# SP3_PMIC.net
KiCad netlist of a schematic drawn in Altium Designer
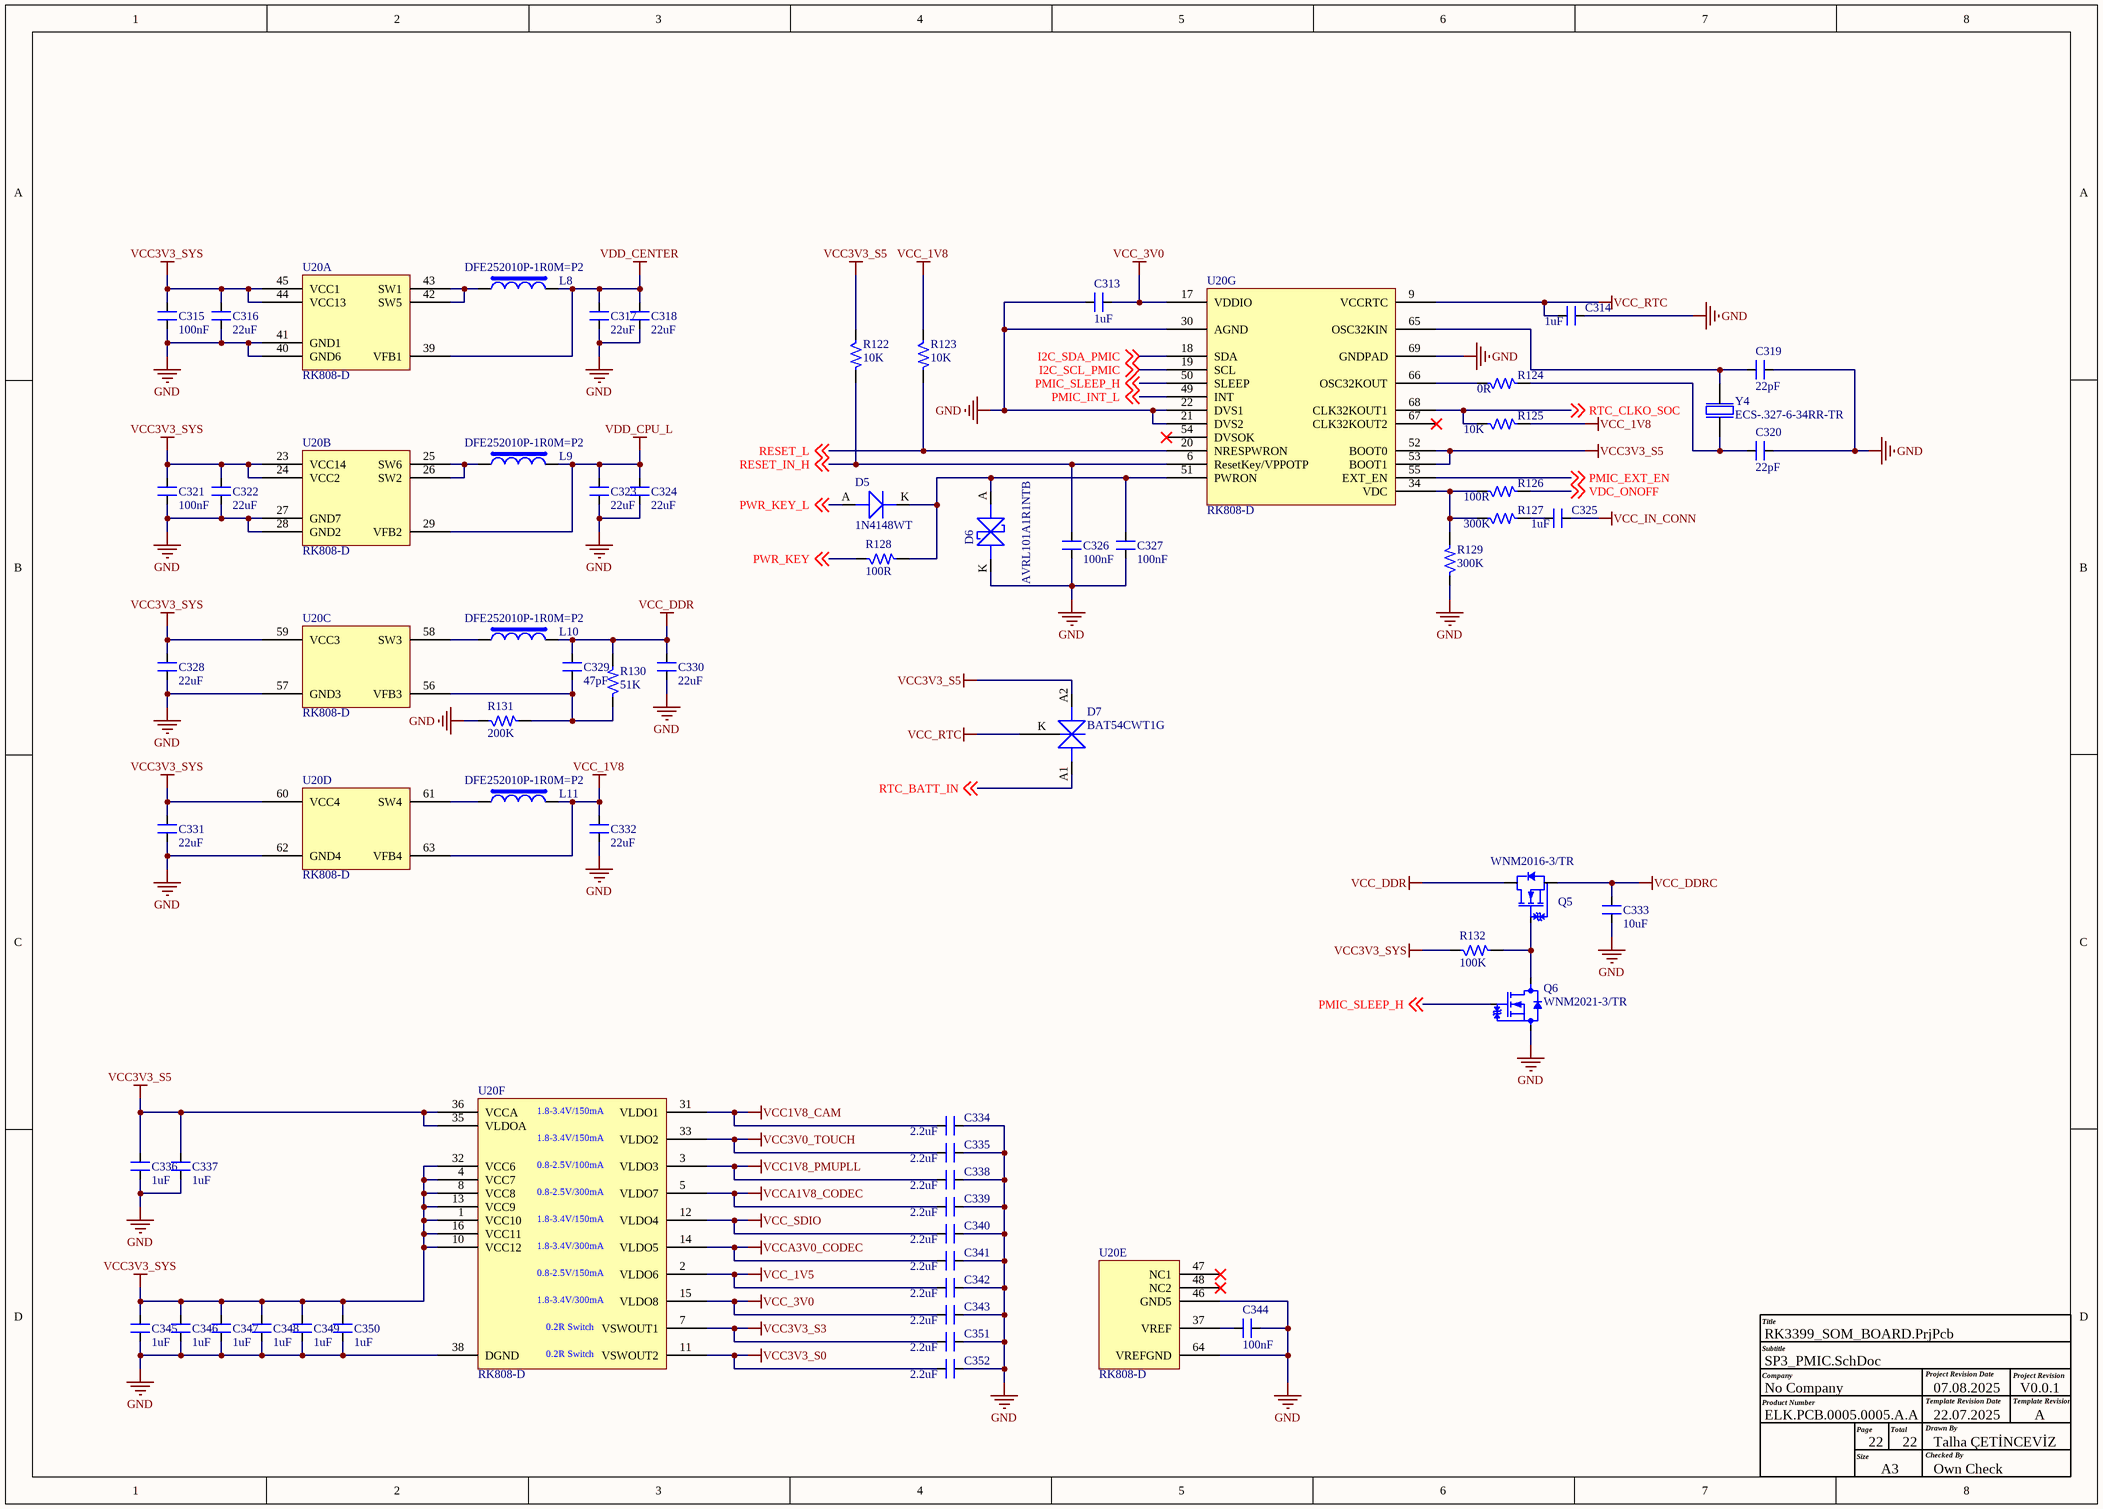
[diagram p0: SP3_PMIC.SchDoc]

(export (version "E")
  (design (tool "Eeschema 10.0.6"))
  (components
    (comp (ref "C313")
      (value "1uF")
      (footprint "CAP_0402")
      (description "1µF ±10% 16V Ceramic Capacitor X5R 0402 (1005 Metric)")
      (fields
        (field (name "MANUFACTURER") "Knowles Novacap")
        (field (name "MANUFACTURER PART NUMBER") "0402BW105K160YT")
      )
      (libsource (lib "EsteemPCB_SOM_Course_intlib") (part "CAP_1uF-16V-10%-0402"))
    )
    (comp (ref "C314")
      (value "1uF")
      (footprint "CAP_0402")
      (description "1µF ±10% 16V Ceramic Capacitor X5R 0402 (1005 Metric)")
      (fields
        (field (name "MANUFACTURER") "Knowles Novacap")
        (field (name "MANUFACTURER PART NUMBER") "0402BW105K160YT")
      )
      (libsource (lib "EsteemPCB_SOM_Course_intlib") (part "CAP_1uF-16V-10%-0402"))
    )
    (comp (ref "C315")
      (value "100nF")
      (footprint "CAP_0402")
      (description "0.1µF ±10% 25V Ceramic Capacitor X7R 0402 (1005 Metric)")
      (fields
        (field (name "MANUFACTURER") "Walsin Technology Corporation")
        (field (name "MANUFACTURER PART NUMBER") "0402B104K250CT")
      )
      (libsource (lib "EsteemPCB_SOM_Course_intlib") (part "CAP_100nF-25V-10%-0402"))
    )
    (comp (ref "C316")
      (value "22uF")
      (footprint "CAP_0603")
      (description "22µF ±20% 10V Ceramic Capacitor X5R 0603 (1608 Metric)")
      (fields
        (field (name "MANUFACTURER") "Murata Electronics")
        (field (name "MANUFACTURER PART NUMBER") "GRM188R61A226ME15D")
      )
      (libsource (lib "EsteemPCB_SOM_Course_intlib") (part "CAP_22uF-10V-20%-0603"))
    )
    (comp (ref "C317")
      (value "22uF")
      (footprint "CAP_0603")
      (description "22µF ±20% 10V Ceramic Capacitor X5R 0603 (1608 Metric)")
      (fields
        (field (name "MANUFACTURER") "Murata Electronics")
        (field (name "MANUFACTURER PART NUMBER") "GRM188R61A226ME15D")
      )
      (libsource (lib "EsteemPCB_SOM_Course_intlib") (part "CAP_22uF-10V-20%-0603"))
    )
    (comp (ref "C318")
      (value "22uF")
      (footprint "CAP_0603")
      (description "22µF ±20% 10V Ceramic Capacitor X5R 0603 (1608 Metric)")
      (fields
        (field (name "MANUFACTURER") "Murata Electronics")
        (field (name "MANUFACTURER PART NUMBER") "GRM188R61A226ME15D")
      )
      (libsource (lib "EsteemPCB_SOM_Course_intlib") (part "CAP_22uF-10V-20%-0603"))
    )
    (comp (ref "C319")
      (value "22pF")
      (footprint "CAP_0402")
      (description "22pF ±10% 10V Ceramic Capacitor C0G, NP0 0402 (1005 Metric)")
      (fields
        (field (name "MANUFACTURER") "KEMET")
        (field (name "MANUFACTURER PART NUMBER") "C0402C220K8GACTU")
      )
      (libsource (lib "EsteemPCB_SOM_Course_intlib") (part "CAP_22pF-10V-10%-0402"))
    )
    (comp (ref "C320")
      (value "22pF")
      (footprint "CAP_0402")
      (description "22pF ±10% 10V Ceramic Capacitor C0G, NP0 0402 (1005 Metric)")
      (fields
        (field (name "MANUFACTURER") "KEMET")
        (field (name "MANUFACTURER PART NUMBER") "C0402C220K8GACTU")
      )
      (libsource (lib "EsteemPCB_SOM_Course_intlib") (part "CAP_22pF-10V-10%-0402"))
    )
    (comp (ref "C321")
      (value "100nF")
      (footprint "CAP_0402")
      (description "0.1µF ±10% 25V Ceramic Capacitor X7R 0402 (1005 Metric)")
      (fields
        (field (name "MANUFACTURER") "Walsin Technology Corporation")
        (field (name "MANUFACTURER PART NUMBER") "0402B104K250CT")
      )
      (libsource (lib "EsteemPCB_SOM_Course_intlib") (part "CAP_100nF-25V-10%-0402"))
    )
    (comp (ref "C322")
      (value "22uF")
      (footprint "CAP_0603")
      (description "22µF ±20% 10V Ceramic Capacitor X5R 0603 (1608 Metric)")
      (fields
        (field (name "MANUFACTURER") "Murata Electronics")
        (field (name "MANUFACTURER PART NUMBER") "GRM188R61A226ME15D")
      )
      (libsource (lib "EsteemPCB_SOM_Course_intlib") (part "CAP_22uF-10V-20%-0603"))
    )
    (comp (ref "C323")
      (value "22uF")
      (footprint "CAP_0603")
      (description "22µF ±20% 10V Ceramic Capacitor X5R 0603 (1608 Metric)")
      (fields
        (field (name "MANUFACTURER") "Murata Electronics")
        (field (name "MANUFACTURER PART NUMBER") "GRM188R61A226ME15D")
      )
      (libsource (lib "EsteemPCB_SOM_Course_intlib") (part "CAP_22uF-10V-20%-0603"))
    )
    (comp (ref "C324")
      (value "22uF")
      (footprint "CAP_0603")
      (description "22µF ±20% 10V Ceramic Capacitor X5R 0603 (1608 Metric)")
      (fields
        (field (name "MANUFACTURER") "Murata Electronics")
        (field (name "MANUFACTURER PART NUMBER") "GRM188R61A226ME15D")
      )
      (libsource (lib "EsteemPCB_SOM_Course_intlib") (part "CAP_22uF-10V-20%-0603"))
    )
    (comp (ref "C325")
      (value "1uF")
      (footprint "CAP_0402")
      (description "1µF ±10% 16V Ceramic Capacitor X5R 0402 (1005 Metric)")
      (fields
        (field (name "MANUFACTURER") "Knowles Novacap")
        (field (name "MANUFACTURER PART NUMBER") "0402BW105K160YT")
      )
      (libsource (lib "EsteemPCB_SOM_Course_intlib") (part "CAP_1uF-16V-10%-0402"))
    )
    (comp (ref "C326")
      (value "100nF")
      (footprint "CAP_0402")
      (description "0.1µF ±10% 25V Ceramic Capacitor X7R 0402 (1005 Metric)")
      (fields
        (field (name "MANUFACTURER") "Walsin Technology Corporation")
        (field (name "MANUFACTURER PART NUMBER") "0402B104K250CT")
      )
      (libsource (lib "EsteemPCB_SOM_Course_intlib") (part "CAP_100nF-25V-10%-0402"))
    )
    (comp (ref "C327")
      (value "100nF")
      (footprint "CAP_0402")
      (description "0.1µF ±10% 25V Ceramic Capacitor X7R 0402 (1005 Metric)")
      (fields
        (field (name "MANUFACTURER") "Walsin Technology Corporation")
        (field (name "MANUFACTURER PART NUMBER") "0402B104K250CT")
      )
      (libsource (lib "EsteemPCB_SOM_Course_intlib") (part "CAP_100nF-25V-10%-0402"))
    )
    (comp (ref "C328")
      (value "22uF")
      (footprint "CAP_0603")
      (description "22µF ±20% 10V Ceramic Capacitor X5R 0603 (1608 Metric)")
      (fields
        (field (name "MANUFACTURER") "Murata Electronics")
        (field (name "MANUFACTURER PART NUMBER") "GRM188R61A226ME15D")
      )
      (libsource (lib "EsteemPCB_SOM_Course_intlib") (part "CAP_22uF-10V-20%-0603"))
    )
    (comp (ref "C329")
      (value "47pF")
      (footprint "CAP_0402")
      (description "47pF ±10% 10V Ceramic Capacitor C0G, NP0 0402 (1005 Metric)")
      (fields
        (field (name "MANUFACTURER") "KEMET")
        (field (name "MANUFACTURER PART NUMBER") "C0402C470K8GAC7867")
      )
      (libsource (lib "EsteemPCB_SOM_Course_intlib") (part "CAP_47pF-10V-10%-0402"))
    )
    (comp (ref "C330")
      (value "22uF")
      (footprint "CAP_0603")
      (description "22µF ±20% 10V Ceramic Capacitor X5R 0603 (1608 Metric)")
      (fields
        (field (name "MANUFACTURER") "Murata Electronics")
        (field (name "MANUFACTURER PART NUMBER") "GRM188R61A226ME15D")
      )
      (libsource (lib "EsteemPCB_SOM_Course_intlib") (part "CAP_22uF-10V-20%-0603"))
    )
    (comp (ref "C331")
      (value "22uF")
      (footprint "CAP_0603")
      (description "22µF ±20% 10V Ceramic Capacitor X5R 0603 (1608 Metric)")
      (fields
        (field (name "MANUFACTURER") "Murata Electronics")
        (field (name "MANUFACTURER PART NUMBER") "GRM188R61A226ME15D")
      )
      (libsource (lib "EsteemPCB_SOM_Course_intlib") (part "CAP_22uF-10V-20%-0603"))
    )
    (comp (ref "C332")
      (value "22uF")
      (footprint "CAP_0603")
      (description "22µF ±20% 10V Ceramic Capacitor X5R 0603 (1608 Metric)")
      (fields
        (field (name "MANUFACTURER") "Murata Electronics")
        (field (name "MANUFACTURER PART NUMBER") "GRM188R61A226ME15D")
      )
      (libsource (lib "EsteemPCB_SOM_Course_intlib") (part "CAP_22uF-10V-20%-0603"))
    )
    (comp (ref "C333")
      (value "10uF")
      (footprint "CAP_0402")
      (description "10µF ±20% 10V Ceramic Capacitor X5R 0402 (1005 Metric)")
      (fields
        (field (name "MANUFACTURER PART NUMBER") "CL05A106MP5NUNC")
        (field (name "MANUFACTURER") "Samsung Electro-Mechanics")
      )
      (libsource (lib "EsteemPCB_SOM_Course_intlib") (part "CAP_10uF-10V-20%-0402"))
    )
    (comp (ref "C334")
      (value "2.2uF")
      (footprint "CAP_0402")
      (description "2.2µF ±10% 10V Ceramic Capacitor X5R 0402 (1005 Metric)")
      (fields
        (field (name "MANUFACTURER") "Murata Electronics")
        (field (name "MANUFACTURER PART NUMBER") "GRM155R61A225KE95D")
      )
      (libsource (lib "EsteemPCB_SOM_Course_intlib") (part "CAP_2.2uF-10V-10%-0402"))
    )
    (comp (ref "C335")
      (value "2.2uF")
      (footprint "CAP_0402")
      (description "2.2µF ±10% 10V Ceramic Capacitor X5R 0402 (1005 Metric)")
      (fields
        (field (name "MANUFACTURER") "Murata Electronics")
        (field (name "MANUFACTURER PART NUMBER") "GRM155R61A225KE95D")
      )
      (libsource (lib "EsteemPCB_SOM_Course_intlib") (part "CAP_2.2uF-10V-10%-0402"))
    )
    (comp (ref "C336")
      (value "1uF")
      (footprint "CAP_0402")
      (description "1µF ±10% 16V Ceramic Capacitor X5R 0402 (1005 Metric)")
      (fields
        (field (name "MANUFACTURER") "Knowles Novacap")
        (field (name "MANUFACTURER PART NUMBER") "0402BW105K160YT")
      )
      (libsource (lib "EsteemPCB_SOM_Course_intlib") (part "CAP_1uF-16V-10%-0402"))
    )
    (comp (ref "C337")
      (value "1uF")
      (footprint "CAP_0402")
      (description "1µF ±10% 16V Ceramic Capacitor X5R 0402 (1005 Metric)")
      (fields
        (field (name "MANUFACTURER") "Knowles Novacap")
        (field (name "MANUFACTURER PART NUMBER") "0402BW105K160YT")
      )
      (libsource (lib "EsteemPCB_SOM_Course_intlib") (part "CAP_1uF-16V-10%-0402"))
    )
    (comp (ref "C338")
      (value "2.2uF")
      (footprint "CAP_0402")
      (description "2.2µF ±10% 10V Ceramic Capacitor X5R 0402 (1005 Metric)")
      (fields
        (field (name "MANUFACTURER") "Murata Electronics")
        (field (name "MANUFACTURER PART NUMBER") "GRM155R61A225KE95D")
      )
      (libsource (lib "EsteemPCB_SOM_Course_intlib") (part "CAP_2.2uF-10V-10%-0402"))
    )
    (comp (ref "C339")
      (value "2.2uF")
      (footprint "CAP_0402")
      (description "2.2µF ±10% 10V Ceramic Capacitor X5R 0402 (1005 Metric)")
      (fields
        (field (name "MANUFACTURER") "Murata Electronics")
        (field (name "MANUFACTURER PART NUMBER") "GRM155R61A225KE95D")
      )
      (libsource (lib "EsteemPCB_SOM_Course_intlib") (part "CAP_2.2uF-10V-10%-0402"))
    )
    (comp (ref "C340")
      (value "2.2uF")
      (footprint "CAP_0402")
      (description "2.2µF ±10% 10V Ceramic Capacitor X5R 0402 (1005 Metric)")
      (fields
        (field (name "MANUFACTURER") "Murata Electronics")
        (field (name "MANUFACTURER PART NUMBER") "GRM155R61A225KE95D")
      )
      (libsource (lib "EsteemPCB_SOM_Course_intlib") (part "CAP_2.2uF-10V-10%-0402"))
    )
    (comp (ref "C341")
      (value "2.2uF")
      (footprint "CAP_0402")
      (description "2.2µF ±10% 10V Ceramic Capacitor X5R 0402 (1005 Metric)")
      (fields
        (field (name "MANUFACTURER") "Murata Electronics")
        (field (name "MANUFACTURER PART NUMBER") "GRM155R61A225KE95D")
      )
      (libsource (lib "EsteemPCB_SOM_Course_intlib") (part "CAP_2.2uF-10V-10%-0402"))
    )
    (comp (ref "C342")
      (value "2.2uF")
      (footprint "CAP_0402")
      (description "2.2µF ±10% 10V Ceramic Capacitor X5R 0402 (1005 Metric)")
      (fields
        (field (name "MANUFACTURER") "Murata Electronics")
        (field (name "MANUFACTURER PART NUMBER") "GRM155R61A225KE95D")
      )
      (libsource (lib "EsteemPCB_SOM_Course_intlib") (part "CAP_2.2uF-10V-10%-0402"))
    )
    (comp (ref "C343")
      (value "2.2uF")
      (footprint "CAP_0402")
      (description "2.2µF ±10% 10V Ceramic Capacitor X5R 0402 (1005 Metric)")
      (fields
        (field (name "MANUFACTURER") "Murata Electronics")
        (field (name "MANUFACTURER PART NUMBER") "GRM155R61A225KE95D")
      )
      (libsource (lib "EsteemPCB_SOM_Course_intlib") (part "CAP_2.2uF-10V-10%-0402"))
    )
    (comp (ref "C344")
      (value "100nF")
      (footprint "CAP_0402")
      (description "0.1µF ±10% 25V Ceramic Capacitor X7R 0402 (1005 Metric)")
      (fields
        (field (name "MANUFACTURER") "Walsin Technology Corporation")
        (field (name "MANUFACTURER PART NUMBER") "0402B104K250CT")
      )
      (libsource (lib "EsteemPCB_SOM_Course_intlib") (part "CAP_100nF-25V-10%-0402"))
    )
    (comp (ref "C345")
      (value "1uF")
      (footprint "CAP_0402")
      (description "1µF ±10% 16V Ceramic Capacitor X5R 0402 (1005 Metric)")
      (fields
        (field (name "MANUFACTURER") "Knowles Novacap")
        (field (name "MANUFACTURER PART NUMBER") "0402BW105K160YT")
      )
      (libsource (lib "EsteemPCB_SOM_Course_intlib") (part "CAP_1uF-16V-10%-0402"))
    )
    (comp (ref "C346")
      (value "1uF")
      (footprint "CAP_0402")
      (description "1µF ±10% 16V Ceramic Capacitor X5R 0402 (1005 Metric)")
      (fields
        (field (name "MANUFACTURER") "Knowles Novacap")
        (field (name "MANUFACTURER PART NUMBER") "0402BW105K160YT")
      )
      (libsource (lib "EsteemPCB_SOM_Course_intlib") (part "CAP_1uF-16V-10%-0402"))
    )
    (comp (ref "C347")
      (value "1uF")
      (footprint "CAP_0402")
      (description "1µF ±10% 16V Ceramic Capacitor X5R 0402 (1005 Metric)")
      (fields
        (field (name "MANUFACTURER") "Knowles Novacap")
        (field (name "MANUFACTURER PART NUMBER") "0402BW105K160YT")
      )
      (libsource (lib "EsteemPCB_SOM_Course_intlib") (part "CAP_1uF-16V-10%-0402"))
    )
    (comp (ref "C348")
      (value "1uF")
      (footprint "CAP_0402")
      (description "1µF ±10% 16V Ceramic Capacitor X5R 0402 (1005 Metric)")
      (fields
        (field (name "MANUFACTURER") "Knowles Novacap")
        (field (name "MANUFACTURER PART NUMBER") "0402BW105K160YT")
      )
      (libsource (lib "EsteemPCB_SOM_Course_intlib") (part "CAP_1uF-16V-10%-0402"))
    )
    (comp (ref "C349")
      (value "1uF")
      (footprint "CAP_0402")
      (description "1µF ±10% 16V Ceramic Capacitor X5R 0402 (1005 Metric)")
      (fields
        (field (name "MANUFACTURER") "Knowles Novacap")
        (field (name "MANUFACTURER PART NUMBER") "0402BW105K160YT")
      )
      (libsource (lib "EsteemPCB_SOM_Course_intlib") (part "CAP_1uF-16V-10%-0402"))
    )
    (comp (ref "C350")
      (value "1uF")
      (footprint "CAP_0402")
      (description "1µF ±10% 16V Ceramic Capacitor X5R 0402 (1005 Metric)")
      (fields
        (field (name "MANUFACTURER") "Knowles Novacap")
        (field (name "MANUFACTURER PART NUMBER") "0402BW105K160YT")
      )
      (libsource (lib "EsteemPCB_SOM_Course_intlib") (part "CAP_1uF-16V-10%-0402"))
    )
    (comp (ref "C351")
      (value "2.2uF")
      (footprint "CAP_0402")
      (description "2.2µF ±10% 10V Ceramic Capacitor X5R 0402 (1005 Metric)")
      (fields
        (field (name "MANUFACTURER") "Murata Electronics")
        (field (name "MANUFACTURER PART NUMBER") "GRM155R61A225KE95D")
      )
      (libsource (lib "EsteemPCB_SOM_Course_intlib") (part "CAP_2.2uF-10V-10%-0402"))
    )
    (comp (ref "C352")
      (value "2.2uF")
      (footprint "CAP_0402")
      (description "2.2µF ±10% 10V Ceramic Capacitor X5R 0402 (1005 Metric)")
      (fields
        (field (name "MANUFACTURER") "Murata Electronics")
        (field (name "MANUFACTURER PART NUMBER") "GRM155R61A225KE95D")
      )
      (libsource (lib "EsteemPCB_SOM_Course_intlib") (part "CAP_2.2uF-10V-10%-0402"))
    )
    (comp (ref "D5")
      (value "1N4148WT")
      (footprint "DIO_SOD523")
      (description "Diode Standard 100V 300mA (DC) Surface Mount SOD-123")
      (fields (field (name "MANUFACTURER") "FAIRCHILD"))
      (libsource (lib "EsteemPCB_SOM_Course_intlib") (part "DIO_75V-200mA-SOD-523F"))
    )
    (comp (ref "D6")
      (value "AVRL101A1R1NTB")
      (footprint "DIO_0402_SMD")
      (description "39V Varistor 1 Circuit Surface Mount, MLCV 0402 (1005 Metric)")
      (fields (field (name "MANUFACTURER") "TDK Corporation"))
      (libsource (lib "EsteemPCB_SOM_Course_intlib") (part "DIO-T_10V-39V-0402"))
    )
    (comp (ref "D7")
      (value "BAT54CWT1G")
      (footprint "DIO_SOT-323-3")
      (description "Diode Array 1 Pair Common Cathode Schottky 30V 200mA (DC) Surface Mount SC-70, SOT-323")
      (fields (field (name "MANUFACTURER") "ON Semiconductor"))
      (libsource (lib "EsteemPCB_SOM_Course_intlib") (part "DIO-S-A_30V-200mA-SOT-323"))
    )
    (comp (ref "L8")
      (value "DFE252010P-1R0M=P2")
      (footprint "IND_1008")
      (description "1µH Shielded Wirewound Inductor 3.8A 54mOhm Max 1008 (2520 Metric)")
      (fields (field (name "MANUFACTURER") "Murata Electronics"))
      (libsource (lib "EsteemPCB_SOM_Course_intlib") (part "IND_1uH-3.8A-20%-1008"))
    )
    (comp (ref "L9")
      (value "DFE252010P-1R0M=P2")
      (footprint "IND_1008")
      (description "1µH Shielded Wirewound Inductor 3.8A 54mOhm Max 1008 (2520 Metric)")
      (fields (field (name "MANUFACTURER") "Murata Electronics"))
      (libsource (lib "EsteemPCB_SOM_Course_intlib") (part "IND_1uH-3.8A-20%-1008"))
    )
    (comp (ref "L10")
      (value "DFE252010P-1R0M=P2")
      (footprint "IND_1008")
      (description "1µH Shielded Wirewound Inductor 3.8A 54mOhm Max 1008 (2520 Metric)")
      (fields (field (name "MANUFACTURER") "Murata Electronics"))
      (libsource (lib "EsteemPCB_SOM_Course_intlib") (part "IND_1uH-3.8A-20%-1008"))
    )
    (comp (ref "L11")
      (value "DFE252010P-1R0M=P2")
      (footprint "IND_1008")
      (description "1µH Shielded Wirewound Inductor 3.8A 54mOhm Max 1008 (2520 Metric)")
      (fields (field (name "MANUFACTURER") "Murata Electronics"))
      (libsource (lib "EsteemPCB_SOM_Course_intlib") (part "IND_1uH-3.8A-20%-1008"))
    )
    (comp (ref "Q5")
      (value "WNM2016-3/TR")
      (footprint "SOT 23-3")
      (description "N Channel 20V 2.9A 1V @ 250uA 47mΩ @ 3.6A,4.5V 700mW SOT-23(SOT-23-3) MOSFET RoHS")
      (fields (field (name "MANUFACTURER") "WILLSEMI(Will Semicon)"))
      (libsource (lib "EsteemPCB_SOM_Course_intlib") (part "MOSFET-N_20V-2.9A-SOT-23"))
    )
    (comp (ref "Q6")
      (value "WNM2021-3/TR")
      (footprint "SOT-323-3")
      (description "N Channel 20V 820mA 850mV @ 250uA 310mΩ @ 550mA,4.5V 310mW SOT-323(SC-70) MOSFET RoHS")
      (fields (field (name "MANUFACTURER") "WILLSEMI(Will Semicon)"))
      (libsource (lib "EsteemPCB_SOM_Course_intlib") (part "MOSFET-N_20V-820mA-SOT-323"))
    )
    (comp (ref "R122")
      (value "10K")
      (footprint "RES_0402")
      (description "10 kOhms ±1% 0.1W, 1/10W Chip Resistor 0402 (1005 Metric) Anti-Sulfur Thin Film")
      (fields
        (field (name "MANUFACTURER") "Vishay Beyschlag/Draloric/BC Components")
        (field (name "MANUFACTURER PART NUMBER") "MCS04020C1002FE000")
      )
      (libsource (lib "EsteemPCB_SOM_Course_intlib") (part "RES_10K-0.1W-1%-0402"))
    )
    (comp (ref "R123")
      (value "10K")
      (footprint "RES_0402")
      (description "10 kOhms ±1% 0.1W, 1/10W Chip Resistor 0402 (1005 Metric) Anti-Sulfur Thin Film")
      (fields
        (field (name "MANUFACTURER") "Vishay Beyschlag/Draloric/BC Components")
        (field (name "MANUFACTURER PART NUMBER") "MCS04020C1002FE000")
      )
      (libsource (lib "EsteemPCB_SOM_Course_intlib") (part "RES_10K-0.1W-1%-0402"))
    )
    (comp (ref "R124")
      (value "0R")
      (footprint "RES_0402")
      (description "0 Ohms Jumper 0.1W, 1/10W Chip Resistor 0402 (1005 Metric) Automotive AEC-Q200 Thick Film")
      (fields
        (field (name "MANUFACTURER") "Panasonic Electronic Components")
        (field (name "MANUFACTURER PART NUMBER") "ERJ-2GE0R00X")
      )
      (libsource (lib "EsteemPCB_SOM_Course_intlib") (part "RES_0R-0.1W-1%-0402"))
    )
    (comp (ref "R125")
      (value "10K")
      (footprint "RES_0402")
      (description "10 kOhms ±1% 0.1W, 1/10W Chip Resistor 0402 (1005 Metric) Anti-Sulfur Thin Film")
      (fields
        (field (name "MANUFACTURER") "Vishay Beyschlag/Draloric/BC Components")
        (field (name "MANUFACTURER PART NUMBER") "MCS04020C1002FE000")
      )
      (libsource (lib "EsteemPCB_SOM_Course_intlib") (part "RES_10K-0.1W-1%-0402"))
    )
    (comp (ref "R126")
      (value "100R")
      (footprint "RES_0402")
      (fields
        (field (name "MANUFACTURER") "KOA Speer Electronics, Inc.")
        (field (name "MANUFACTURER PART NUMBER") "RK73H1ETTP1000F")
      )
      (libsource (lib "EsteemPCB_SOM_Course_intlib") (part "RES_100R-0.1W-1%-0402"))
    )
    (comp (ref "R127")
      (value "300K")
      (footprint "RES_0402")
      (description "300 kOhms ±1% 0.1W, 1/10W Chip Resistor 0402 (1005 Metric) Automotive AEC-Q200 Thick Film")
      (fields
        (field (name "MANUFACTURER") "Panasonic Electronic Components")
        (field (name "MANUFACTURER PART NUMBER") "ERJ-2RKF3003X")
      )
      (libsource (lib "EsteemPCB_SOM_Course_intlib") (part "RES_300K-0.1W-1%-0402"))
    )
    (comp (ref "R128")
      (value "100R")
      (footprint "RES_0402")
      (fields
        (field (name "MANUFACTURER") "KOA Speer Electronics, Inc.")
        (field (name "MANUFACTURER PART NUMBER") "RK73H1ETTP1000F")
      )
      (libsource (lib "EsteemPCB_SOM_Course_intlib") (part "RES_100R-0.1W-1%-0402"))
    )
    (comp (ref "R129")
      (value "300K")
      (footprint "RES_0402")
      (description "300 kOhms ±1% 0.1W, 1/10W Chip Resistor 0402 (1005 Metric) Automotive AEC-Q200 Thick Film")
      (fields
        (field (name "MANUFACTURER") "Panasonic Electronic Components")
        (field (name "MANUFACTURER PART NUMBER") "ERJ-2RKF3003X")
      )
      (libsource (lib "EsteemPCB_SOM_Course_intlib") (part "RES_300K-0.1W-1%-0402"))
    )
    (comp (ref "R130")
      (value "51K")
      (footprint "RES_0402")
      (description "51 kOhms ±1% 0.1W, 1/10W Chip Resistor 0402 (1005 Metric) Automotive AEC-Q200 Thick Film")
      (fields
        (field (name "MANUFACTURER") "Panasonic Electronic Components")
        (field (name "MANUFACTURER PART NUMBER") "ERJ-2RKF5102X")
      )
      (libsource (lib "EsteemPCB_SOM_Course_intlib") (part "RES_51K-0.1W-1%-0402"))
    )
    (comp (ref "R131")
      (value "200K")
      (footprint "RES_0402")
      (description "200 kOhms ±1% 0.1W, 1/10W Chip Resistor 0402 (1005 Metric) Automotive AEC-Q200 Thick Film")
      (fields
        (field (name "MANUFACTURER") "Panasonic Electronic Components")
        (field (name "MANUFACTURER PART NUMBER") "ERJ-2RKF2003X")
      )
      (libsource (lib "EsteemPCB_SOM_Course_intlib") (part "RES_200K-0.1W-1%-0402"))
    )
    (comp (ref "R132")
      (value "100K")
      (footprint "RES_0402")
      (description "100 kOhms ±1% 0.1W, 1/10W Chip Resistor 0402 (1005 Metric) Anti-Sulfur Thin Film")
      (fields
        (field (name "MANUFACTURER") "Vishay Beyschlag/Draloric/BC Components")
        (field (name "MANUFACTURER PART NUMBER") "MCS04020C1003FE000")
      )
      (libsource (lib "EsteemPCB_SOM_Course_intlib") (part "RES_100K-0.1W-1%-0402"))
    )
    (comp (ref "U20")
      (value "RK808-D")
      (footprint "QFN68_13.7_220.4X220.4_SMD")
      (description "The RK808 is a complete power supply solution for Portable systems.")
      (fields (field (name "MANUFACTURER") "Rockchip"))
      (libsource (lib "") (part "IC_RK808-D-QFN68_3"))
    )
    (comp (ref "Y4")
      (value "ECS-.327-6-34RR-TR")
      (footprint "XTAL_ECS-.327-6-34RR-TR")
      (description "32.768kHz ±20ppm Crystal 12pF 80 kOhms 2-SMD, No Lead")
      (fields (field (name "MANUFACTURER") "Ecliptek"))
      (libsource (lib "EsteemPCB_SOM_Course_intlib") (part "XTAL_32.768Khz-22pF-SMD"))
    )
  )
  (nets
    (net (code "1") (name "GND") (class "Default")
      (node (ref "C313") (pin "2") (pinfunction "2_2") (pintype "passive"))
      (node (ref "C314") (pin "1") (pinfunction "1_1") (pintype "passive"))
      (node (ref "C315") (pin "1") (pinfunction "1_1") (pintype "passive"))
      (node (ref "C316") (pin "1") (pinfunction "1_1") (pintype "passive"))
      (node (ref "C317") (pin "1") (pinfunction "1_1") (pintype "passive"))
      (node (ref "C318") (pin "1") (pinfunction "1_1") (pintype "passive"))
      (node (ref "C319") (pin "1") (pinfunction "1_1") (pintype "passive"))
      (node (ref "C320") (pin "1") (pinfunction "1_1") (pintype "passive"))
      (node (ref "C321") (pin "1") (pinfunction "1_1") (pintype "passive"))
      (node (ref "C322") (pin "1") (pinfunction "1_1") (pintype "passive"))
      (node (ref "C323") (pin "1") (pinfunction "1_1") (pintype "passive"))
      (node (ref "C324") (pin "1") (pinfunction "1_1") (pintype "passive"))
      (node (ref "C326") (pin "1") (pinfunction "1_1") (pintype "passive"))
      (node (ref "C327") (pin "1") (pinfunction "1_1") (pintype "passive"))
      (node (ref "C328") (pin "1") (pinfunction "1_1") (pintype "passive"))
      (node (ref "C330") (pin "1") (pinfunction "1_1") (pintype "passive"))
      (node (ref "C331") (pin "1") (pinfunction "1_1") (pintype "passive"))
      (node (ref "C332") (pin "1") (pinfunction "1_1") (pintype "passive"))
      (node (ref "C333") (pin "1") (pinfunction "1_1") (pintype "passive"))
      (node (ref "C334") (pin "2") (pinfunction "2_2") (pintype "passive"))
      (node (ref "C335") (pin "2") (pinfunction "2_2") (pintype "passive"))
      (node (ref "C336") (pin "1") (pinfunction "1_1") (pintype "passive"))
      (node (ref "C337") (pin "1") (pinfunction "1_1") (pintype "passive"))
      (node (ref "C338") (pin "2") (pinfunction "2_2") (pintype "passive"))
      (node (ref "C339") (pin "2") (pinfunction "2_2") (pintype "passive"))
      (node (ref "C340") (pin "2") (pinfunction "2_2") (pintype "passive"))
      (node (ref "C341") (pin "2") (pinfunction "2_2") (pintype "passive"))
      (node (ref "C342") (pin "2") (pinfunction "2_2") (pintype "passive"))
      (node (ref "C343") (pin "2") (pinfunction "2_2") (pintype "passive"))
      (node (ref "C344") (pin "1") (pinfunction "1_1") (pintype "passive"))
      (node (ref "C345") (pin "1") (pinfunction "1_1") (pintype "passive"))
      (node (ref "C346") (pin "1") (pinfunction "1_1") (pintype "passive"))
      (node (ref "C347") (pin "1") (pinfunction "1_1") (pintype "passive"))
      (node (ref "C348") (pin "1") (pinfunction "1_1") (pintype "passive"))
      (node (ref "C349") (pin "1") (pinfunction "1_1") (pintype "passive"))
      (node (ref "C350") (pin "1") (pinfunction "1_1") (pintype "passive"))
      (node (ref "C351") (pin "2") (pinfunction "2_2") (pintype "passive"))
      (node (ref "C352") (pin "2") (pinfunction "2_2") (pintype "passive"))
      (node (ref "D6") (pin "K") (pinfunction "K_K") (pintype "passive"))
      (node (ref "Q6") (pin "2") (pinfunction "S_2") (pintype "passive"))
      (node (ref "R129") (pin "1") (pinfunction "1_1") (pintype "passive"))
      (node (ref "R131") (pin "1") (pinfunction "1_1") (pintype "passive"))
      (node (ref "U20") (pin "21") (pinfunction "DVS2_21") (pintype "passive"))
      (node (ref "U20") (pin "22") (pinfunction "DVS1_22") (pintype "passive"))
      (node (ref "U20") (pin "27") (pinfunction "GND7_27") (pintype "passive"))
      (node (ref "U20") (pin "28") (pinfunction "GND2_28") (pintype "passive"))
      (node (ref "U20") (pin "30") (pinfunction "AGND_30") (pintype "passive"))
      (node (ref "U20") (pin "38") (pinfunction "DGND_38") (pintype "passive"))
      (node (ref "U20") (pin "40") (pinfunction "GND6_40") (pintype "passive"))
      (node (ref "U20") (pin "41") (pinfunction "GND1_41") (pintype "passive"))
      (node (ref "U20") (pin "46") (pinfunction "GND5_46") (pintype "passive"))
      (node (ref "U20") (pin "57") (pinfunction "GND3_57") (pintype "passive"))
      (node (ref "U20") (pin "62") (pinfunction "GND4_62") (pintype "passive"))
      (node (ref "U20") (pin "64") (pinfunction "VREFGND_64") (pintype "passive"))
      (node (ref "U20") (pin "69") (pinfunction "GNDPAD_69") (pintype "passive"))
    )
    (net (code "2") (name "I2C_SCL_PMIC") (class "Default")
      (node (ref "U20") (pin "19") (pinfunction "SCL_19") (pintype "passive"))
    )
    (net (code "3") (name "I2C_SDA_PMIC") (class "Default")
      (node (ref "U20") (pin "18") (pinfunction "SDA_18") (pintype "passive"))
    )
    (net (code "4") (name "Net-(C320-Pad2)") (class "Default")
      (node (ref "C320") (pin "2") (pinfunction "2_2") (pintype "passive"))
      (node (ref "R124") (pin "2") (pinfunction "2_2") (pintype "passive"))
      (node (ref "Y4") (pin "2") (pinfunction "2_2") (pintype "passive"))
    )
    (net (code "5") (name "Net-(C325-Pad2)") (class "Default")
      (node (ref "C325") (pin "2") (pinfunction "2_2") (pintype "passive"))
      (node (ref "R127") (pin "2") (pinfunction "2_2") (pintype "passive"))
    )
    (net (code "6") (name "Net-(D5-CATHODE)") (class "Default")
      (node (ref "C327") (pin "2") (pinfunction "2_2") (pintype "passive"))
      (node (ref "D5") (pin "K") (pinfunction "CATHODE_K") (pintype "passive"))
      (node (ref "D6") (pin "A") (pinfunction "A_A") (pintype "passive"))
      (node (ref "R128") (pin "2") (pinfunction "2_2") (pintype "passive"))
      (node (ref "U20") (pin "51") (pinfunction "PWRON_51") (pintype "passive"))
    )
    (net (code "7") (name "Net-(Q5-G)") (class "Default")
      (node (ref "Q5") (pin "1") (pinfunction "G_1") (pintype "passive"))
      (node (ref "Q6") (pin "3") (pinfunction "D_3") (pintype "passive"))
      (node (ref "R132") (pin "2") (pinfunction "2_2") (pintype "passive"))
    )
    (net (code "8") (name "Net-(U20A-SW1)") (class "Default")
      (node (ref "L8") (pin "1") (pinfunction "1_1") (pintype "passive"))
      (node (ref "U20") (pin "42") (pinfunction "SW5_42") (pintype "passive"))
      (node (ref "U20") (pin "43") (pinfunction "SW1_43") (pintype "passive"))
    )
    (net (code "9") (name "Net-(U20B-SW2)") (class "Default")
      (node (ref "L9") (pin "1") (pinfunction "1_1") (pintype "passive"))
      (node (ref "U20") (pin "25") (pinfunction "SW6_25") (pintype "passive"))
      (node (ref "U20") (pin "26") (pinfunction "SW2_26") (pintype "passive"))
    )
    (net (code "10") (name "Net-(U20C-SW3)") (class "Default")
      (node (ref "L10") (pin "1") (pinfunction "1_1") (pintype "passive"))
      (node (ref "U20") (pin "58") (pinfunction "SW3_58") (pintype "passive"))
    )
    (net (code "11") (name "Net-(U20C-VFB3)") (class "Default")
      (node (ref "C329") (pin "1") (pinfunction "1_1") (pintype "passive"))
      (node (ref "R130") (pin "1") (pinfunction "1_1") (pintype "passive"))
      (node (ref "R131") (pin "2") (pinfunction "2_2") (pintype "passive"))
      (node (ref "U20") (pin "56") (pinfunction "VFB3_56") (pintype "passive"))
    )
    (net (code "12") (name "Net-(U20D-SW4)") (class "Default")
      (node (ref "L11") (pin "1") (pinfunction "1_1") (pintype "passive"))
      (node (ref "U20") (pin "61") (pinfunction "SW4_61") (pintype "passive"))
    )
    (net (code "13") (name "Net-(U20E-VREF)") (class "Default")
      (node (ref "C344") (pin "2") (pinfunction "2_2") (pintype "passive"))
      (node (ref "U20") (pin "37") (pinfunction "VREF_37") (pintype "passive"))
    )
    (net (code "14") (name "Net-(U20G-OSC32KIN)") (class "Default")
      (node (ref "C319") (pin "2") (pinfunction "2_2") (pintype "passive"))
      (node (ref "U20") (pin "65") (pinfunction "OSC32KIN_65") (pintype "passive"))
      (node (ref "Y4") (pin "1") (pinfunction "1_1") (pintype "passive"))
    )
    (net (code "15") (name "Net-(U20G-OSC32KOUT)") (class "Default")
      (node (ref "R124") (pin "1") (pinfunction "1_1") (pintype "passive"))
      (node (ref "U20") (pin "66") (pinfunction "OSC32KOUT_66") (pintype "passive"))
    )
    (net (code "16") (name "Net-(U20G-VDC)") (class "Default")
      (node (ref "R126") (pin "1") (pinfunction "1_1") (pintype "passive"))
      (node (ref "R127") (pin "1") (pinfunction "1_1") (pintype "passive"))
      (node (ref "R129") (pin "2") (pinfunction "2_2") (pintype "passive"))
      (node (ref "U20") (pin "34") (pinfunction "VDC_34") (pintype "passive"))
    )
    (net (code "17") (name "PMIC_EXT_EN") (class "Default")
      (node (ref "U20") (pin "55") (pinfunction "EXT_EN_55") (pintype "passive"))
    )
    (net (code "18") (name "PMIC_INT_L") (class "Default")
      (node (ref "U20") (pin "49") (pinfunction "INT_49") (pintype "passive"))
    )
    (net (code "19") (name "PMIC_SLEEP_H") (class "Default")
      (node (ref "Q6") (pin "1") (pinfunction "G_1") (pintype "passive"))
      (node (ref "U20") (pin "50") (pinfunction "SLEEP_50") (pintype "passive"))
    )
    (net (code "20") (name "PWR_KEY") (class "Default")
      (node (ref "R128") (pin "1") (pinfunction "1_1") (pintype "passive"))
    )
    (net (code "21") (name "PWR_KEY_L") (class "Default")
      (node (ref "D5") (pin "A") (pinfunction "ANODE_A") (pintype "passive"))
    )
    (net (code "22") (name "RESET_IN_H") (class "Default")
      (node (ref "C326") (pin "2") (pinfunction "2_2") (pintype "passive"))
      (node (ref "R122") (pin "2") (pinfunction "2_2") (pintype "passive"))
      (node (ref "U20") (pin "6") (pinfunction "ResetKey/VPPOTP_6") (pintype "passive"))
    )
    (net (code "23") (name "RESET_L") (class "Default")
      (node (ref "R123") (pin "2") (pinfunction "2_2") (pintype "passive"))
      (node (ref "U20") (pin "20") (pinfunction "NRESPWRON_20") (pintype "passive"))
    )
    (net (code "24") (name "RTC_BATT_IN") (class "Default")
      (node (ref "D7") (pin "A1") (pinfunction "A1_A1") (pintype "passive"))
    )
    (net (code "25") (name "RTC_CLKO_SOC") (class "Default")
      (node (ref "R125") (pin "1") (pinfunction "1_1") (pintype "passive"))
      (node (ref "U20") (pin "68") (pinfunction "CLK32KOUT1_68") (pintype "passive"))
    )
    (net (code "26") (name "VCC1V8_CAM") (class "Default")
      (node (ref "C334") (pin "1") (pinfunction "1_1") (pintype "passive"))
      (node (ref "U20") (pin "31") (pinfunction "VLDO1_31") (pintype "passive"))
    )
    (net (code "27") (name "VCC1V8_PMUPLL") (class "Default")
      (node (ref "C338") (pin "1") (pinfunction "1_1") (pintype "passive"))
      (node (ref "U20") (pin "3") (pinfunction "VLDO3_3") (pintype "passive"))
    )
    (net (code "28") (name "VCC3V0_TOUCH") (class "Default")
      (node (ref "C335") (pin "1") (pinfunction "1_1") (pintype "passive"))
      (node (ref "U20") (pin "33") (pinfunction "VLDO2_33") (pintype "passive"))
    )
    (net (code "29") (name "VCC3V3_S0") (class "Default")
      (node (ref "C352") (pin "1") (pinfunction "1_1") (pintype "passive"))
      (node (ref "U20") (pin "11") (pinfunction "VSWOUT2_11") (pintype "passive"))
    )
    (net (code "30") (name "VCC3V3_S3") (class "Default")
      (node (ref "C351") (pin "1") (pinfunction "1_1") (pintype "passive"))
      (node (ref "U20") (pin "7") (pinfunction "VSWOUT1_7") (pintype "passive"))
    )
    (net (code "31") (name "VCC3V3_S5") (class "Default")
      (node (ref "C336") (pin "2") (pinfunction "2_2") (pintype "passive"))
      (node (ref "C337") (pin "2") (pinfunction "2_2") (pintype "passive"))
      (node (ref "D7") (pin "A2") (pinfunction "A2_A2") (pintype "passive"))
      (node (ref "R122") (pin "1") (pinfunction "1_1") (pintype "passive"))
      (node (ref "U20") (pin "35") (pinfunction "VLDOA_35") (pintype "passive"))
      (node (ref "U20") (pin "36") (pinfunction "VCCA_36") (pintype "passive"))
      (node (ref "U20") (pin "52") (pinfunction "BOOT0_52") (pintype "passive"))
      (node (ref "U20") (pin "53") (pinfunction "BOOT1_53") (pintype "passive"))
    )
    (net (code "32") (name "VCC3V3_SYS") (class "Default")
      (node (ref "C315") (pin "2") (pinfunction "2_2") (pintype "passive"))
      (node (ref "C316") (pin "2") (pinfunction "2_2") (pintype "passive"))
      (node (ref "C321") (pin "2") (pinfunction "2_2") (pintype "passive"))
      (node (ref "C322") (pin "2") (pinfunction "2_2") (pintype "passive"))
      (node (ref "C328") (pin "2") (pinfunction "2_2") (pintype "passive"))
      (node (ref "C331") (pin "2") (pinfunction "2_2") (pintype "passive"))
      (node (ref "C345") (pin "2") (pinfunction "2_2") (pintype "passive"))
      (node (ref "C346") (pin "2") (pinfunction "2_2") (pintype "passive"))
      (node (ref "C347") (pin "2") (pinfunction "2_2") (pintype "passive"))
      (node (ref "C348") (pin "2") (pinfunction "2_2") (pintype "passive"))
      (node (ref "C349") (pin "2") (pinfunction "2_2") (pintype "passive"))
      (node (ref "C350") (pin "2") (pinfunction "2_2") (pintype "passive"))
      (node (ref "R132") (pin "1") (pinfunction "1_1") (pintype "passive"))
      (node (ref "U20") (pin "1") (pinfunction "VCC10_1") (pintype "passive"))
      (node (ref "U20") (pin "10") (pinfunction "VCC12_10") (pintype "passive"))
      (node (ref "U20") (pin "13") (pinfunction "VCC9_13") (pintype "passive"))
      (node (ref "U20") (pin "16") (pinfunction "VCC11_16") (pintype "passive"))
      (node (ref "U20") (pin "23") (pinfunction "VCC14_23") (pintype "passive"))
      (node (ref "U20") (pin "24") (pinfunction "VCC2_24") (pintype "passive"))
      (node (ref "U20") (pin "32") (pinfunction "VCC6_32") (pintype "passive"))
      (node (ref "U20") (pin "4") (pinfunction "VCC7_4") (pintype "passive"))
      (node (ref "U20") (pin "44") (pinfunction "VCC13_44") (pintype "passive"))
      (node (ref "U20") (pin "45") (pinfunction "VCC1_45") (pintype "passive"))
      (node (ref "U20") (pin "59") (pinfunction "VCC3_59") (pintype "passive"))
      (node (ref "U20") (pin "60") (pinfunction "VCC4_60") (pintype "passive"))
      (node (ref "U20") (pin "8") (pinfunction "VCC8_8") (pintype "passive"))
    )
    (net (code "33") (name "VCCA1V8_CODEC") (class "Default")
      (node (ref "C339") (pin "1") (pinfunction "1_1") (pintype "passive"))
      (node (ref "U20") (pin "5") (pinfunction "VLDO7_5") (pintype "passive"))
    )
    (net (code "34") (name "VCCA3V0_CODEC") (class "Default")
      (node (ref "C341") (pin "1") (pinfunction "1_1") (pintype "passive"))
      (node (ref "U20") (pin "14") (pinfunction "VLDO5_14") (pintype "passive"))
    )
    (net (code "35") (name "VCC_1V5") (class "Default")
      (node (ref "C342") (pin "1") (pinfunction "1_1") (pintype "passive"))
      (node (ref "U20") (pin "2") (pinfunction "VLDO6_2") (pintype "passive"))
    )
    (net (code "36") (name "VCC_1V8") (class "Default")
      (node (ref "C332") (pin "2") (pinfunction "2_2") (pintype "passive"))
      (node (ref "L11") (pin "2") (pinfunction "2_2") (pintype "passive"))
      (node (ref "R123") (pin "1") (pinfunction "1_1") (pintype "passive"))
      (node (ref "R125") (pin "2") (pinfunction "2_2") (pintype "passive"))
      (node (ref "U20") (pin "63") (pinfunction "VFB4_63") (pintype "passive"))
    )
    (net (code "37") (name "VCC_3V0") (class "Default")
      (node (ref "C313") (pin "1") (pinfunction "1_1") (pintype "passive"))
      (node (ref "C343") (pin "1") (pinfunction "1_1") (pintype "passive"))
      (node (ref "U20") (pin "15") (pinfunction "VLDO8_15") (pintype "passive"))
      (node (ref "U20") (pin "17") (pinfunction "VDDIO_17") (pintype "passive"))
    )
    (net (code "38") (name "VCC_DDR") (class "Default")
      (node (ref "C329") (pin "2") (pinfunction "2_2") (pintype "passive"))
      (node (ref "C330") (pin "2") (pinfunction "2_2") (pintype "passive"))
      (node (ref "L10") (pin "2") (pinfunction "2_2") (pintype "passive"))
      (node (ref "Q5") (pin "3") (pinfunction "D_3") (pintype "passive"))
      (node (ref "R130") (pin "2") (pinfunction "2_2") (pintype "passive"))
    )
    (net (code "39") (name "VCC_DDRC") (class "Default")
      (node (ref "C333") (pin "2") (pinfunction "2_2") (pintype "passive"))
      (node (ref "Q5") (pin "2") (pinfunction "S_2") (pintype "passive"))
    )
    (net (code "40") (name "VCC_IN_CONN") (class "Default")
      (node (ref "C325") (pin "1") (pinfunction "1_1") (pintype "passive"))
    )
    (net (code "41") (name "VCC_RTC") (class "Default")
      (node (ref "C314") (pin "2") (pinfunction "2_2") (pintype "passive"))
      (node (ref "D7") (pin "K") (pinfunction "K_K") (pintype "passive"))
      (node (ref "U20") (pin "9") (pinfunction "VCCRTC_9") (pintype "passive"))
    )
    (net (code "42") (name "VCC_SDIO") (class "Default")
      (node (ref "C340") (pin "1") (pinfunction "1_1") (pintype "passive"))
      (node (ref "U20") (pin "12") (pinfunction "VLDO4_12") (pintype "passive"))
    )
    (net (code "43") (name "VDC_ONOFF") (class "Default")
      (node (ref "R126") (pin "2") (pinfunction "2_2") (pintype "passive"))
    )
    (net (code "44") (name "VDD_CENTER") (class "Default")
      (node (ref "C317") (pin "2") (pinfunction "2_2") (pintype "passive"))
      (node (ref "C318") (pin "2") (pinfunction "2_2") (pintype "passive"))
      (node (ref "L8") (pin "2") (pinfunction "2_2") (pintype "passive"))
      (node (ref "U20") (pin "39") (pinfunction "VFB1_39") (pintype "passive"))
    )
    (net (code "45") (name "VDD_CPU_L") (class "Default")
      (node (ref "C323") (pin "2") (pinfunction "2_2") (pintype "passive"))
      (node (ref "C324") (pin "2") (pinfunction "2_2") (pintype "passive"))
      (node (ref "L9") (pin "2") (pinfunction "2_2") (pintype "passive"))
      (node (ref "U20") (pin "29") (pinfunction "VFB2_29") (pintype "passive"))
    )
    (net (code "46") (name "unconnected-(U20E-NC1-Pad47)") (class "Default")
      (node (ref "U20") (pin "47") (pinfunction "NC1_47") (pintype "passive+no_connect"))
    )
    (net (code "47") (name "unconnected-(U20E-NC2-Pad48)") (class "Default")
      (node (ref "U20") (pin "48") (pinfunction "NC2_48") (pintype "passive+no_connect"))
    )
    (net (code "48") (name "unconnected-(U20G-CLK32KOUT2-Pad67)") (class "Default")
      (node (ref "U20") (pin "67") (pinfunction "CLK32KOUT2_67") (pintype "passive+no_connect"))
    )
    (net (code "49") (name "unconnected-(U20G-DVSOK-Pad54)") (class "Default")
      (node (ref "U20") (pin "54") (pinfunction "DVSOK_54") (pintype "passive+no_connect"))
    )
  )
)
